# Sheet1.net
KiCad netlist of a schematic drawn in Altium Designer
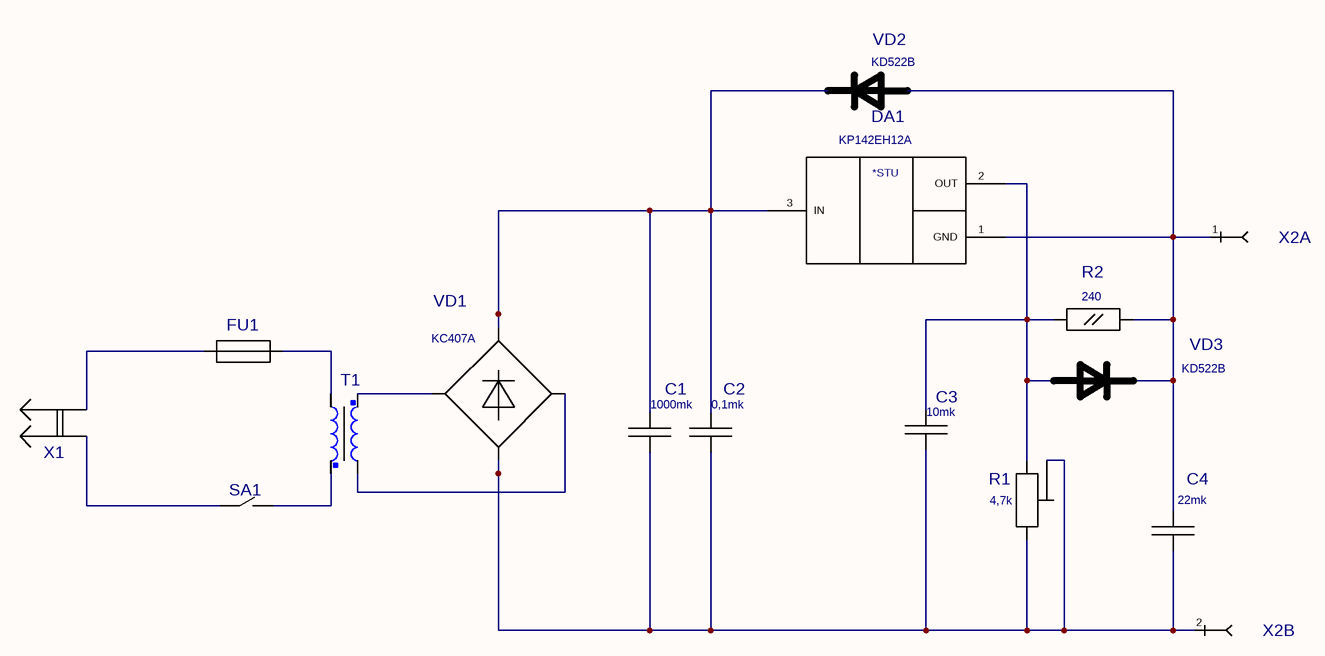
[diagram p0: Sheet1.SCHDOC]

(export (version "E")
  (design (tool "Eeschema 10.0.6"))
  (components
    (comp (ref "C1")
      (value "1000mk")
      (footprint "1017-B3R")
      (description "1017-B3R")
      (libsource (lib "*") (part "1017-B3R"))
    )
    (comp (ref "C2")
      (value "0,1mk")
      (footprint "1017-B3R")
      (description "1017-B3R")
      (libsource (lib "*") (part "1017-B3R"))
    )
    (comp (ref "C3")
      (value "10mk")
      (footprint "1017-B3R")
      (description "1017-B3R")
      (libsource (lib "*") (part "1017-B3R"))
    )
    (comp (ref "C4")
      (value "22mk")
      (footprint "1017-B3R")
      (description "1017-B3R")
      (libsource (lib "*") (part "1017-B3R"))
    )
    (comp (ref "DA1")
      (value "KP142EH12A")
      (footprint "TO-220-KT-28-2")
      (description "КР142ЕН12А")
      (libsource (lib "*") (part "КР142ЕН12А"))
    )
    (comp (ref "FU1") (value "FH-101C") (footprint "FH-101C") (libsource (lib "*") (part "FH-101C")))
    (comp (ref "R1")
      (value "4,7k")
      (footprint "SP5-16-025")
      (description "СП5-16-0,25")
      (libsource (lib "*") (part "СП5-16-0,25"))
    )
    (comp (ref "R2")
      (value "240")
      (footprint "C2-33H-0.125W")
      (description "C2-33H-0.125W_OLD_UGO")
      (fields (field (name "AUTOR") "pcbdesigner.ru"))
      (libsource (lib "*") (part "C2-33H-0.125W_OLD_UGO"))
    )
    (comp (ref "SA1")
      (value "8AS9M2RE")
      (footprint "8AS9M2RE")
      (fields (field (name "AUTHOR") "pcbdesigner.ru"))
      (libsource (lib "*") (part "8AS9M2RE"))
    )
    (comp (ref "T1")
      (value "ДФПК30-2/Х")
      (footprint "ДФПК30-2/Х")
      (fields (field (name "AUTHOR") "pcbdesigner.ru"))
      (libsource (lib "*") (part "ДФПК30-2/Х"))
    )
    (comp (ref "VD1")
      (value "KC407A")
      (footprint "KC407")
      (description "KC407")
      (libsource (lib "*") (part "KC407"))
    )
    (comp (ref "VD2")
      (value "KD522B")
      (footprint "КД521(522)")
      (description "КД522Б")
      (libsource (lib "*") (part "КД522Б"))
    )
    (comp (ref "VD3")
      (value "KD522B")
      (footprint "КД521(522)")
      (description "КД522Б")
      (libsource (lib "*") (part "КД522Б"))
    )
    (comp (ref "X1") (value "2XR") (footprint "2XR") (libsource (lib "*") (part "2XR")))
    (comp (ref "X2") (value "30FMN") (footprint "30FMN") (libsource (lib "*") (part "30FMN")))
  )
  (nets
    (net (code "1") (name "Net-(C1-I{slash}OA)") (class "Default")
      (node (ref "C1") (pin "1") (pinfunction "I/OA_1") (pintype "passive"))
      (node (ref "C2") (pin "1") (pinfunction "I/OA_1") (pintype "passive"))
      (node (ref "DA1") (pin "3") (pinfunction "IN_3") (pintype "passive"))
      (node (ref "VD1") (pin "3") (pinfunction "I/O3_3") (pintype "passive"))
      (node (ref "VD1") (pin "4") (pinfunction "I/O4_4") (pintype "passive"))
      (node (ref "VD2") (pin "2") (pinfunction "K_2") (pintype "passive"))
    )
    (net (code "2") (name "Net-(C1-I{slash}OB)") (class "Default")
      (node (ref "C1") (pin "2") (pinfunction "I/OB_2") (pintype "passive"))
      (node (ref "C2") (pin "2") (pinfunction "I/OB_2") (pintype "passive"))
      (node (ref "C3") (pin "2") (pinfunction "I/OB_2") (pintype "passive"))
      (node (ref "C4") (pin "2") (pinfunction "I/OB_2") (pintype "passive"))
      (node (ref "R1") (pin "1") (pinfunction "1_1") (pintype "passive"))
      (node (ref "R1") (pin "3") (pinfunction "2_3") (pintype "passive"))
      (node (ref "VD1") (pin "1") (pinfunction "I/O1_1") (pintype "passive"))
      (node (ref "VD1") (pin "6") (pinfunction "I/O6_6") (pintype "passive"))
      (node (ref "X2") (pin "2") (pinfunction "i/o_2") (pintype "passive"))
    )
    (net (code "3") (name "Net-(C3-I{slash}OA)") (class "Default")
      (node (ref "C3") (pin "1") (pinfunction "I/OA_1") (pintype "passive"))
      (node (ref "DA1") (pin "2") (pinfunction "OUT_2") (pintype "passive"))
      (node (ref "R1") (pin "2") (pinfunction "3_2") (pintype "passive"))
      (node (ref "R2") (pin "1") (pinfunction "1_1") (pintype "passive"))
      (node (ref "VD3") (pin "1") (pinfunction "A_1") (pintype "passive"))
    )
    (net (code "4") (name "Net-(C4-I{slash}OA)") (class "Default")
      (node (ref "C4") (pin "1") (pinfunction "I/OA_1") (pintype "passive"))
      (node (ref "DA1") (pin "1") (pinfunction "GND_1") (pintype "passive"))
      (node (ref "R2") (pin "2") (pinfunction "2_2") (pintype "passive"))
      (node (ref "VD2") (pin "1") (pinfunction "A_1") (pintype "passive"))
      (node (ref "VD3") (pin "2") (pinfunction "K_2") (pintype "passive"))
      (node (ref "X2") (pin "1") (pinfunction "i/o_1") (pintype "passive"))
    )
    (net (code "5") (name "Net-(FU1-Pad2)") (class "Default")
      (node (ref "FU1") (pin "2") (pinfunction "2_2") (pintype "passive"))
      (node (ref "T1") (pin "2") (pinfunction "2_2") (pintype "passive"))
    )
    (net (code "6") (name "Net-(SA1-Pad1)") (class "Default")
      (node (ref "SA1") (pin "1") (pinfunction "1_1") (pintype "passive"))
      (node (ref "T1") (pin "1") (pinfunction "1_1") (pintype "passive"))
    )
    (net (code "7") (name "Net-(VD1-I{slash}O2)") (class "Default")
      (node (ref "T1") (pin "4") (pinfunction "4_4") (pintype "passive"))
      (node (ref "VD1") (pin "2") (pinfunction "I/O2_2") (pintype "passive"))
    )
    (net (code "8") (name "Net-(VD1-I{slash}O5)") (class "Default")
      (node (ref "T1") (pin "3") (pinfunction "3_3") (pintype "passive"))
      (node (ref "VD1") (pin "5") (pinfunction "I/O5_5") (pintype "passive"))
    )
    (net (code "9") (name "Net-(X1-I{slash}O1)") (class "Default")
      (node (ref "SA1") (pin "2") (pinfunction "2_2") (pintype "passive"))
      (node (ref "X1") (pin "1") (pinfunction "I/O1_1") (pintype "passive"))
    )
    (net (code "10") (name "Net-(X1-I{slash}O2)") (class "Default")
      (node (ref "FU1") (pin "1") (pinfunction "1_1") (pintype "passive"))
      (node (ref "X1") (pin "2") (pinfunction "I/O2_2") (pintype "passive"))
    )
    (net (code "11") (name "unconnected-(DA1-Pad4)") (class "Default")
      (node (ref "DA1") (pin "4") (pintype "passive"))
    )
  )
)
